# Page_E_Micro_SD.net
KiCad netlist of a schematic drawn in Altium Designer
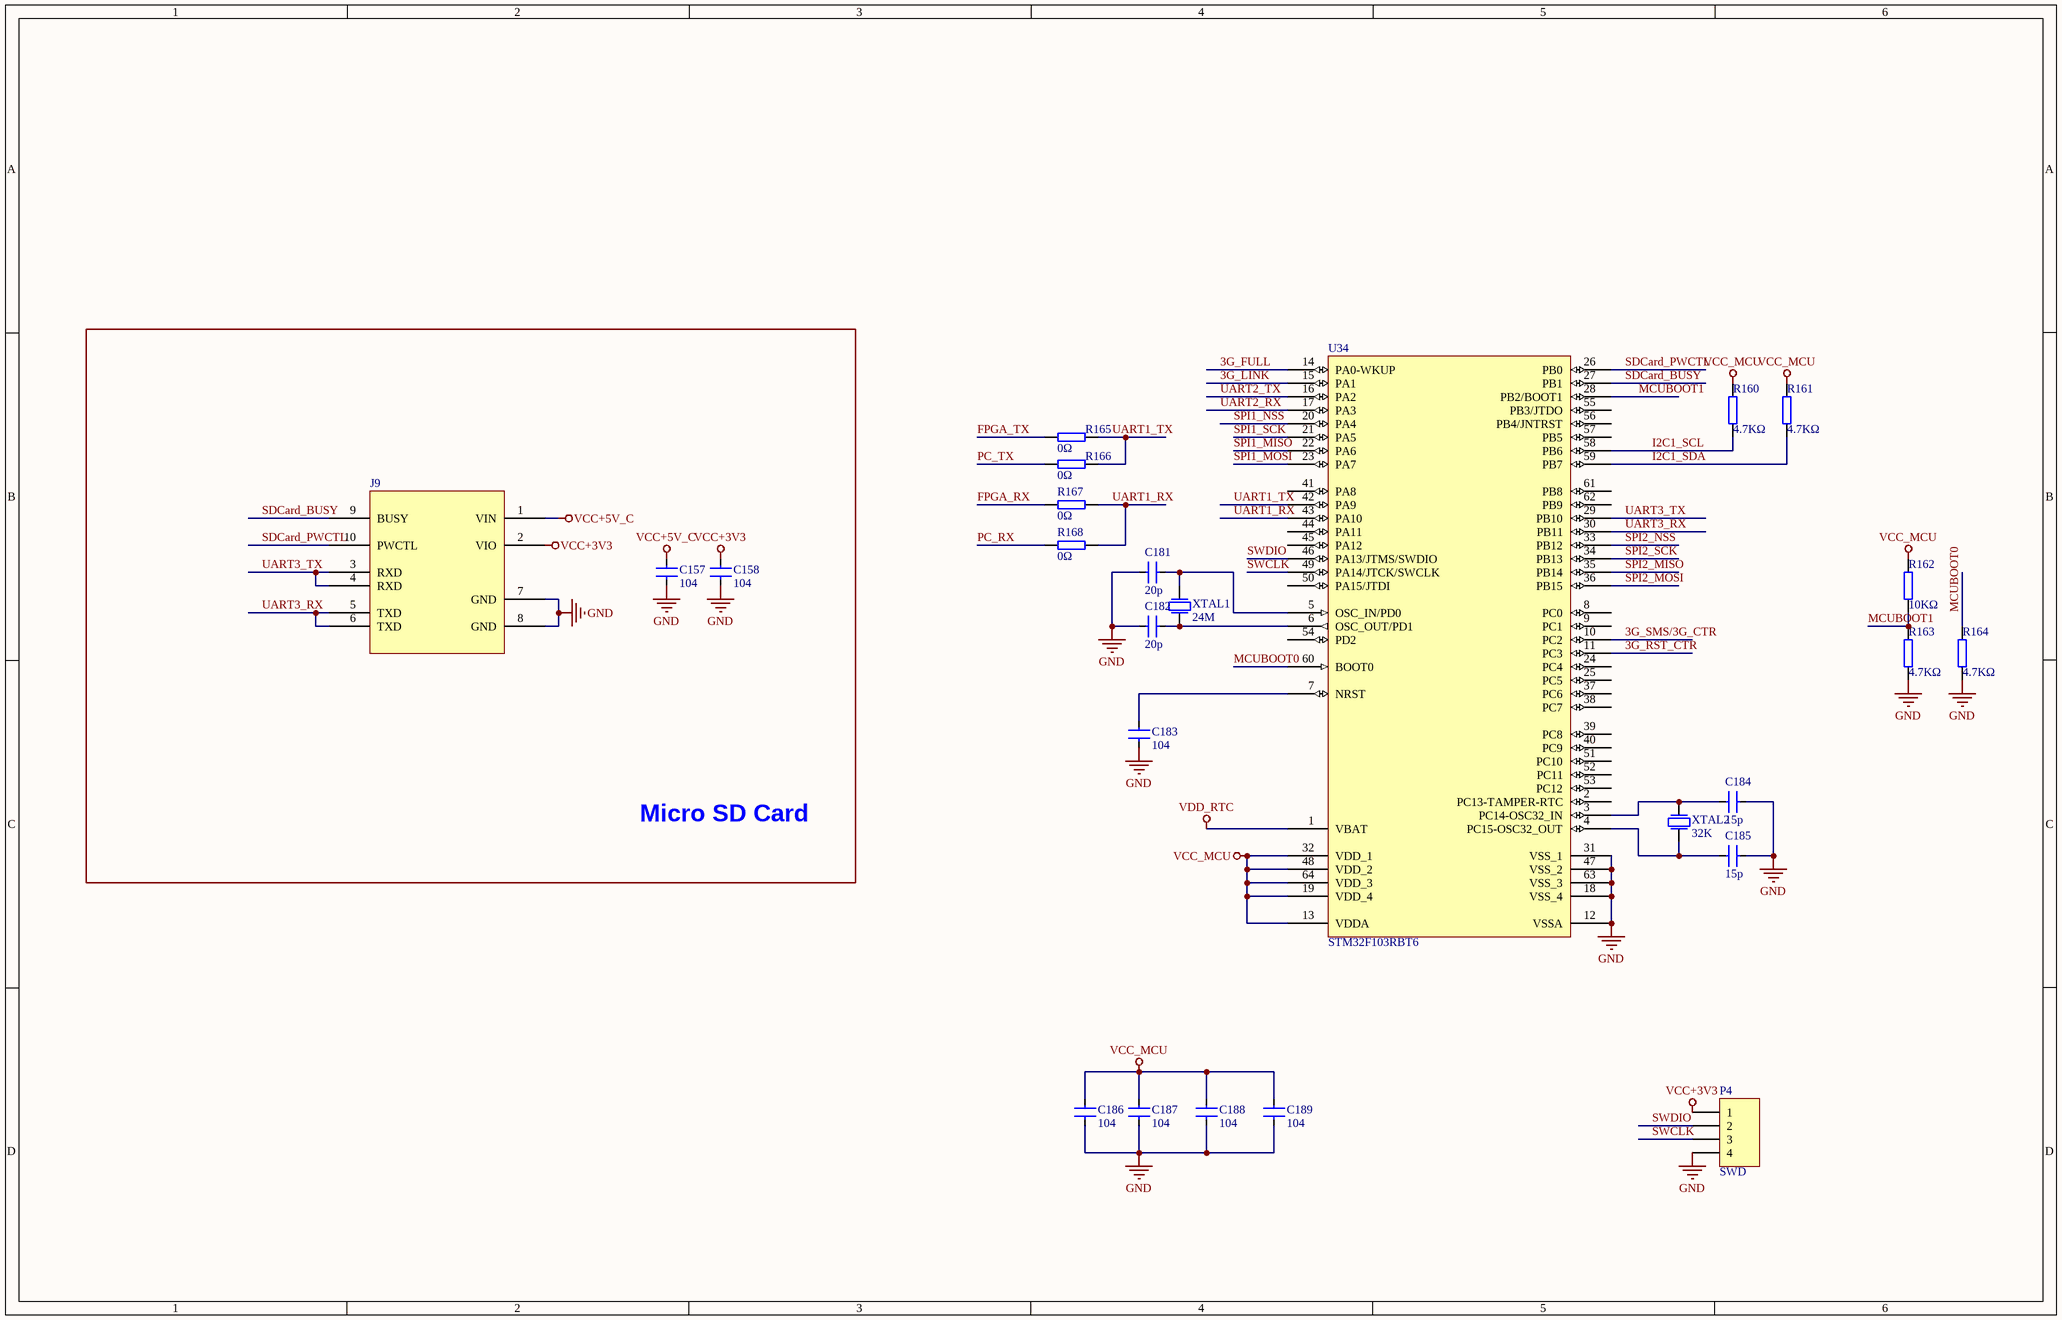
[diagram p0: Page E_Micro_SD.SchDoc]

(export (version "E")
  (design (tool "Eeschema 10.0.6"))
  (components
    (comp (ref "C157")
      (value "104")
      (footprint "0603C")
      (description "C-X5R/X7R")
      (libsource (lib "贴片电阻电容") (part "C-X5R/X7R"))
    )
    (comp (ref "C158")
      (value "104")
      (footprint "0603C")
      (description "C-X5R/X7R")
      (libsource (lib "贴片电阻电容") (part "C-X5R/X7R"))
    )
    (comp (ref "C181")
      (value "20p")
      (footprint "0603C")
      (description "C-X5R/X7R")
      (libsource (lib "贴片电阻电容") (part "C-X5R/X7R"))
    )
    (comp (ref "C182")
      (value "20p")
      (footprint "0603C")
      (description "C-X5R/X7R")
      (libsource (lib "贴片电阻电容") (part "C-X5R/X7R"))
    )
    (comp (ref "C183")
      (value "104")
      (footprint "0603C")
      (description "C-X5R/X7R")
      (libsource (lib "贴片电阻电容") (part "C-X5R/X7R"))
    )
    (comp (ref "C184")
      (value "15p")
      (footprint "0603C")
      (description "C-X5R/X7R")
      (libsource (lib "贴片电阻电容") (part "C-X5R/X7R"))
    )
    (comp (ref "C185")
      (value "15p")
      (footprint "0603C")
      (description "C-X5R/X7R")
      (libsource (lib "贴片电阻电容") (part "C-X5R/X7R"))
    )
    (comp (ref "C186")
      (value "104")
      (footprint "0603C")
      (description "C-X5R/X7R")
      (libsource (lib "贴片电阻电容") (part "C-X5R/X7R"))
    )
    (comp (ref "C187")
      (value "104")
      (footprint "0603C")
      (description "C-X5R/X7R")
      (libsource (lib "贴片电阻电容") (part "C-X5R/X7R"))
    )
    (comp (ref "C188")
      (value "104")
      (footprint "0603C")
      (description "C-X5R/X7R")
      (libsource (lib "贴片电阻电容") (part "C-X5R/X7R"))
    )
    (comp (ref "C189")
      (value "104")
      (footprint "0603C")
      (description "C-X5R/X7R")
      (libsource (lib "贴片电阻电容") (part "C-X5R/X7R"))
    )
    (comp (ref "J9") (value "SDV600") (footprint "JTAG10PW") (libsource (lib "其他元器件") (part "Uart0_SDCard")))
    (comp (ref "P4")
      (value "SWD")
      (footprint "HDR1X4")
      (description "Header, 4-Pin")
      (fields (field (name "PUBLISHER") "Altium Limited"))
      (libsource (lib "Miscellaneous Connectors") (part "Header 4"))
    )
    (comp (ref "R160") (value "4.7KΩ") (footprint "0603R") (libsource (lib "贴片电阻") (part "1K-0805R")))
    (comp (ref "R161") (value "4.7KΩ") (footprint "0603R") (libsource (lib "贴片电阻") (part "1K-0805R")))
    (comp (ref "R162") (value "10KΩ") (footprint "0603R") (libsource (lib "贴片电阻") (part "1K-0805R")))
    (comp (ref "R163") (value "4.7KΩ") (footprint "0603R") (libsource (lib "贴片电阻") (part "1K-0805R")))
    (comp (ref "R164") (value "4.7KΩ") (footprint "0603R") (libsource (lib "贴片电阻") (part "1K-0805R")))
    (comp (ref "R165") (value "0Ω") (footprint "0603R") (libsource (lib "贴片电阻") (part "1K-0805R")))
    (comp (ref "R166") (value "0Ω") (footprint "0603R") (libsource (lib "贴片电阻") (part "1K-0805R")))
    (comp (ref "R167") (value "0Ω") (footprint "0603R") (libsource (lib "贴片电阻") (part "1K-0805R")))
    (comp (ref "R168") (value "0Ω") (footprint "0603R") (libsource (lib "贴片电阻") (part "1K-0805R")))
    (comp (ref "U34")
      (value "STM32F103RBT6")
      (footprint "LQFP64_N")
      (description "STM32 ARM-based 32-bit MCU with 128 Kbytes Flash, 64-pin LQFP, Industrial Temperature")
      (fields (field (name "PUBLISHER") "Altium Limited"))
      (libsource (lib "ST Microcontroller 32-Bit STM32") (part "STM32F103RBT6"))
    )
    (comp (ref "XTAL1")
      (value "24M")
      (footprint "XTAL2")
      (description "CRYSTAL")
      (libsource (lib "xubaolong") (part "XTAL"))
    )
    (comp (ref "XTAL2")
      (value "32K")
      (footprint "XTAL_32.768")
      (description "CRYSTAL")
      (libsource (lib "xubaolong") (part "XTAL"))
    )
  )
  (nets
    (net (code "1") (name "/3G_FULL") (class "Default")
      (node (ref "U34") (pin "14") (pinfunction "PA0-WKUP_14") (pintype "bidirectional"))
    )
    (net (code "2") (name "/3G_LINK") (class "Default")
      (node (ref "U34") (pin "15") (pinfunction "PA1_15") (pintype "bidirectional"))
    )
    (net (code "3") (name "/3G_RST_CTR") (class "Default")
      (node (ref "U34") (pin "11") (pinfunction "PC3_11") (pintype "bidirectional"))
    )
    (net (code "4") (name "/3G_SMS{slash}3G_CTR") (class "Default")
      (node (ref "U34") (pin "10") (pinfunction "PC2_10") (pintype "bidirectional"))
    )
    (net (code "5") (name "/FPGA_RX") (class "Default")
      (node (ref "R167") (pin "1") (pinfunction "1_1") (pintype "passive"))
    )
    (net (code "6") (name "/FPGA_TX") (class "Default")
      (node (ref "R165") (pin "1") (pinfunction "1_1") (pintype "passive"))
    )
    (net (code "7") (name "/I2C1_SCL") (class "Default")
      (node (ref "R160") (pin "2") (pinfunction "2_2") (pintype "passive"))
      (node (ref "U34") (pin "58") (pinfunction "PB6_58") (pintype "bidirectional"))
    )
    (net (code "8") (name "/I2C1_SDA") (class "Default")
      (node (ref "R161") (pin "2") (pinfunction "2_2") (pintype "passive"))
      (node (ref "U34") (pin "59") (pinfunction "PB7_59") (pintype "bidirectional"))
    )
    (net (code "9") (name "/MCUBOOT0") (class "Default")
      (node (ref "R164") (pin "1") (pinfunction "1_1") (pintype "passive"))
      (node (ref "U34") (pin "60") (pinfunction "BOOT0_60") (pintype "input"))
    )
    (net (code "10") (name "/MCUBOOT1") (class "Default")
      (node (ref "R162") (pin "2") (pinfunction "2_2") (pintype "passive"))
      (node (ref "R163") (pin "1") (pinfunction "1_1") (pintype "passive"))
      (node (ref "U34") (pin "28") (pinfunction "PB2/BOOT1_28") (pintype "bidirectional"))
    )
    (net (code "11") (name "/PC_RX") (class "Default")
      (node (ref "R168") (pin "1") (pinfunction "1_1") (pintype "passive"))
    )
    (net (code "12") (name "/PC_TX") (class "Default")
      (node (ref "R166") (pin "1") (pinfunction "1_1") (pintype "passive"))
    )
    (net (code "13") (name "/SDCard_BUSY") (class "Default")
      (node (ref "J9") (pin "9") (pinfunction "BUSY_9") (pintype "passive"))
      (node (ref "U34") (pin "27") (pinfunction "PB1_27") (pintype "bidirectional"))
    )
    (net (code "14") (name "/SDCard_PWCTL") (class "Default")
      (node (ref "J9") (pin "10") (pinfunction "PWCTL_10") (pintype "passive"))
      (node (ref "U34") (pin "26") (pinfunction "PB0_26") (pintype "bidirectional"))
    )
    (net (code "15") (name "/SPI1_MISO") (class "Default")
      (node (ref "U34") (pin "22") (pinfunction "PA6_22") (pintype "bidirectional"))
    )
    (net (code "16") (name "/SPI1_MOSI") (class "Default")
      (node (ref "U34") (pin "23") (pinfunction "PA7_23") (pintype "bidirectional"))
    )
    (net (code "17") (name "/SPI1_NSS") (class "Default")
      (node (ref "U34") (pin "20") (pinfunction "PA4_20") (pintype "bidirectional"))
    )
    (net (code "18") (name "/SPI1_SCK") (class "Default")
      (node (ref "U34") (pin "21") (pinfunction "PA5_21") (pintype "bidirectional"))
    )
    (net (code "19") (name "/SPI2_MISO") (class "Default")
      (node (ref "U34") (pin "35") (pinfunction "PB14_35") (pintype "bidirectional"))
    )
    (net (code "20") (name "/SPI2_MOSI") (class "Default")
      (node (ref "U34") (pin "36") (pinfunction "PB15_36") (pintype "bidirectional"))
    )
    (net (code "21") (name "/SPI2_NSS") (class "Default")
      (node (ref "U34") (pin "33") (pinfunction "PB12_33") (pintype "bidirectional"))
    )
    (net (code "22") (name "/SPI2_SCK") (class "Default")
      (node (ref "U34") (pin "34") (pinfunction "PB13_34") (pintype "bidirectional"))
    )
    (net (code "23") (name "/SWCLK") (class "Default")
      (node (ref "P4") (pin "3") (pinfunction "3_3") (pintype "passive"))
      (node (ref "U34") (pin "49") (pinfunction "PA14/JTCK/SWCLK_49") (pintype "bidirectional"))
    )
    (net (code "24") (name "/SWDIO") (class "Default")
      (node (ref "P4") (pin "2") (pinfunction "2_2") (pintype "passive"))
      (node (ref "U34") (pin "46") (pinfunction "PA13/JTMS/SWDIO_46") (pintype "bidirectional"))
    )
    (net (code "25") (name "/UART1_RX") (class "Default")
      (node (ref "R167") (pin "2") (pinfunction "2_2") (pintype "passive"))
      (node (ref "R168") (pin "2") (pinfunction "2_2") (pintype "passive"))
      (node (ref "U34") (pin "43") (pinfunction "PA10_43") (pintype "bidirectional"))
    )
    (net (code "26") (name "/UART1_TX") (class "Default")
      (node (ref "R165") (pin "2") (pinfunction "2_2") (pintype "passive"))
      (node (ref "R166") (pin "2") (pinfunction "2_2") (pintype "passive"))
      (node (ref "U34") (pin "42") (pinfunction "PA9_42") (pintype "bidirectional"))
    )
    (net (code "27") (name "/UART2_RX") (class "Default")
      (node (ref "U34") (pin "17") (pinfunction "PA3_17") (pintype "bidirectional"))
    )
    (net (code "28") (name "/UART2_TX") (class "Default")
      (node (ref "U34") (pin "16") (pinfunction "PA2_16") (pintype "bidirectional"))
    )
    (net (code "29") (name "/UART3_RX") (class "Default")
      (node (ref "J9") (pin "5") (pinfunction "TXD_5") (pintype "passive"))
      (node (ref "J9") (pin "6") (pinfunction "TXD_6") (pintype "passive"))
      (node (ref "U34") (pin "30") (pinfunction "PB11_30") (pintype "bidirectional"))
    )
    (net (code "30") (name "/UART3_TX") (class "Default")
      (node (ref "J9") (pin "3") (pinfunction "RXD_3") (pintype "passive"))
      (node (ref "J9") (pin "4") (pinfunction "RXD_4") (pintype "passive"))
      (node (ref "U34") (pin "29") (pinfunction "PB10_29") (pintype "bidirectional"))
    )
    (net (code "31") (name "GND") (class "Default")
      (node (ref "C157") (pin "1") (pinfunction "1_1") (pintype "passive"))
      (node (ref "C158") (pin "1") (pinfunction "1_1") (pintype "passive"))
      (node (ref "C181") (pin "2") (pinfunction "2_2") (pintype "passive"))
      (node (ref "C182") (pin "2") (pinfunction "2_2") (pintype "passive"))
      (node (ref "C183") (pin "1") (pinfunction "1_1") (pintype "passive"))
      (node (ref "C184") (pin "1") (pinfunction "1_1") (pintype "passive"))
      (node (ref "C185") (pin "1") (pinfunction "1_1") (pintype "passive"))
      (node (ref "C186") (pin "1") (pinfunction "1_1") (pintype "passive"))
      (node (ref "C187") (pin "1") (pinfunction "1_1") (pintype "passive"))
      (node (ref "C188") (pin "1") (pinfunction "1_1") (pintype "passive"))
      (node (ref "C189") (pin "1") (pinfunction "1_1") (pintype "passive"))
      (node (ref "J9") (pin "7") (pinfunction "GND_7") (pintype "passive"))
      (node (ref "J9") (pin "8") (pinfunction "GND_8") (pintype "passive"))
      (node (ref "P4") (pin "4") (pinfunction "4_4") (pintype "passive"))
      (node (ref "R163") (pin "2") (pinfunction "2_2") (pintype "passive"))
      (node (ref "R164") (pin "2") (pinfunction "2_2") (pintype "passive"))
      (node (ref "U34") (pin "12") (pinfunction "VSSA_12") (pintype "power_in"))
      (node (ref "U34") (pin "18") (pinfunction "VSS_4_18") (pintype "power_in"))
      (node (ref "U34") (pin "31") (pinfunction "VSS_1_31") (pintype "power_in"))
      (node (ref "U34") (pin "47") (pinfunction "VSS_2_47") (pintype "power_in"))
      (node (ref "U34") (pin "63") (pinfunction "VSS_3_63") (pintype "power_in"))
    )
    (net (code "32") (name "Net-(U34-NRST)") (class "Default")
      (node (ref "C183") (pin "2") (pinfunction "2_2") (pintype "passive"))
      (node (ref "U34") (pin "7") (pinfunction "NRST_7") (pintype "bidirectional"))
    )
    (net (code "33") (name "Net-(U34-OSC_IN{slash}PD0)") (class "Default")
      (node (ref "C181") (pin "1") (pinfunction "1_1") (pintype "passive"))
      (node (ref "U34") (pin "5") (pinfunction "OSC_IN/PD0_5") (pintype "input"))
      (node (ref "XTAL1") (pin "1") (pinfunction "P1_1") (pintype "passive"))
    )
    (net (code "34") (name "Net-(U34-OSC_OUT{slash}PD1)") (class "Default")
      (node (ref "C182") (pin "1") (pinfunction "1_1") (pintype "passive"))
      (node (ref "U34") (pin "6") (pinfunction "OSC_OUT/PD1_6") (pintype "output"))
      (node (ref "XTAL1") (pin "2") (pinfunction "P2_2") (pintype "passive"))
    )
    (net (code "35") (name "Net-(U34-PC14-OSC32_IN)") (class "Default")
      (node (ref "C184") (pin "2") (pinfunction "2_2") (pintype "passive"))
      (node (ref "U34") (pin "3") (pinfunction "PC14-OSC32_IN_3") (pintype "bidirectional"))
      (node (ref "XTAL2") (pin "1") (pinfunction "P1_1") (pintype "passive"))
    )
    (net (code "36") (name "Net-(U34-PC15-OSC32_OUT)") (class "Default")
      (node (ref "C185") (pin "2") (pinfunction "2_2") (pintype "passive"))
      (node (ref "U34") (pin "4") (pinfunction "PC15-OSC32_OUT_4") (pintype "bidirectional"))
      (node (ref "XTAL2") (pin "2") (pinfunction "P2_2") (pintype "passive"))
    )
    (net (code "37") (name "VCC+3V3") (class "Default")
      (node (ref "C158") (pin "2") (pinfunction "2_2") (pintype "passive"))
      (node (ref "J9") (pin "2") (pinfunction "VIO_2") (pintype "passive"))
      (node (ref "P4") (pin "1") (pinfunction "1_1") (pintype "passive"))
    )
    (net (code "38") (name "VCC+5V_C") (class "Default")
      (node (ref "C157") (pin "2") (pinfunction "2_2") (pintype "passive"))
      (node (ref "J9") (pin "1") (pinfunction "VIN_1") (pintype "passive"))
    )
    (net (code "39") (name "VCC_MCU") (class "Default")
      (node (ref "C186") (pin "2") (pinfunction "2_2") (pintype "passive"))
      (node (ref "C187") (pin "2") (pinfunction "2_2") (pintype "passive"))
      (node (ref "C188") (pin "2") (pinfunction "2_2") (pintype "passive"))
      (node (ref "C189") (pin "2") (pinfunction "2_2") (pintype "passive"))
      (node (ref "R160") (pin "1") (pinfunction "1_1") (pintype "passive"))
      (node (ref "R161") (pin "1") (pinfunction "1_1") (pintype "passive"))
      (node (ref "R162") (pin "1") (pinfunction "1_1") (pintype "passive"))
      (node (ref "U34") (pin "13") (pinfunction "VDDA_13") (pintype "power_in"))
      (node (ref "U34") (pin "19") (pinfunction "VDD_4_19") (pintype "power_in"))
      (node (ref "U34") (pin "32") (pinfunction "VDD_1_32") (pintype "power_in"))
      (node (ref "U34") (pin "48") (pinfunction "VDD_2_48") (pintype "power_in"))
      (node (ref "U34") (pin "64") (pinfunction "VDD_3_64") (pintype "power_in"))
    )
    (net (code "40") (name "VDD_RTC") (class "Default")
      (node (ref "U34") (pin "1") (pinfunction "VBAT_1") (pintype "power_in"))
    )
    (net (code "41") (name "unconnected-(U34-PA8-Pad41)") (class "Default")
      (node (ref "U34") (pin "41") (pinfunction "PA8_41") (pintype "bidirectional"))
    )
    (net (code "42") (name "unconnected-(U34-PA11-Pad44)") (class "Default")
      (node (ref "U34") (pin "44") (pinfunction "PA11_44") (pintype "bidirectional"))
    )
    (net (code "43") (name "unconnected-(U34-PA12-Pad45)") (class "Default")
      (node (ref "U34") (pin "45") (pinfunction "PA12_45") (pintype "bidirectional"))
    )
    (net (code "44") (name "unconnected-(U34-PA15{slash}JTDI-Pad50)") (class "Default")
      (node (ref "U34") (pin "50") (pinfunction "PA15/JTDI_50") (pintype "bidirectional"))
    )
    (net (code "45") (name "unconnected-(U34-PB3{slash}JTDO-Pad55)") (class "Default")
      (node (ref "U34") (pin "55") (pinfunction "PB3/JTDO_55") (pintype "bidirectional"))
    )
    (net (code "46") (name "unconnected-(U34-PB4{slash}JNTRST-Pad56)") (class "Default")
      (node (ref "U34") (pin "56") (pinfunction "PB4/JNTRST_56") (pintype "bidirectional"))
    )
    (net (code "47") (name "unconnected-(U34-PB5-Pad57)") (class "Default")
      (node (ref "U34") (pin "57") (pinfunction "PB5_57") (pintype "bidirectional"))
    )
    (net (code "48") (name "unconnected-(U34-PB8-Pad61)") (class "Default")
      (node (ref "U34") (pin "61") (pinfunction "PB8_61") (pintype "bidirectional"))
    )
    (net (code "49") (name "unconnected-(U34-PB9-Pad62)") (class "Default")
      (node (ref "U34") (pin "62") (pinfunction "PB9_62") (pintype "bidirectional"))
    )
    (net (code "50") (name "unconnected-(U34-PC0-Pad8)") (class "Default")
      (node (ref "U34") (pin "8") (pinfunction "PC0_8") (pintype "bidirectional"))
    )
    (net (code "51") (name "unconnected-(U34-PC1-Pad9)") (class "Default")
      (node (ref "U34") (pin "9") (pinfunction "PC1_9") (pintype "bidirectional"))
    )
    (net (code "52") (name "unconnected-(U34-PC4-Pad24)") (class "Default")
      (node (ref "U34") (pin "24") (pinfunction "PC4_24") (pintype "bidirectional"))
    )
    (net (code "53") (name "unconnected-(U34-PC5-Pad25)") (class "Default")
      (node (ref "U34") (pin "25") (pinfunction "PC5_25") (pintype "bidirectional"))
    )
    (net (code "54") (name "unconnected-(U34-PC6-Pad37)") (class "Default")
      (node (ref "U34") (pin "37") (pinfunction "PC6_37") (pintype "bidirectional"))
    )
    (net (code "55") (name "unconnected-(U34-PC7-Pad38)") (class "Default")
      (node (ref "U34") (pin "38") (pinfunction "PC7_38") (pintype "bidirectional"))
    )
    (net (code "56") (name "unconnected-(U34-PC8-Pad39)") (class "Default")
      (node (ref "U34") (pin "39") (pinfunction "PC8_39") (pintype "bidirectional"))
    )
    (net (code "57") (name "unconnected-(U34-PC9-Pad40)") (class "Default")
      (node (ref "U34") (pin "40") (pinfunction "PC9_40") (pintype "bidirectional"))
    )
    (net (code "58") (name "unconnected-(U34-PC10-Pad51)") (class "Default")
      (node (ref "U34") (pin "51") (pinfunction "PC10_51") (pintype "bidirectional"))
    )
    (net (code "59") (name "unconnected-(U34-PC11-Pad52)") (class "Default")
      (node (ref "U34") (pin "52") (pinfunction "PC11_52") (pintype "bidirectional"))
    )
    (net (code "60") (name "unconnected-(U34-PC12-Pad53)") (class "Default")
      (node (ref "U34") (pin "53") (pinfunction "PC12_53") (pintype "bidirectional"))
    )
    (net (code "61") (name "unconnected-(U34-PC13-TAMPER-RTC-Pad2)") (class "Default")
      (node (ref "U34") (pin "2") (pinfunction "PC13-TAMPER-RTC_2") (pintype "bidirectional"))
    )
    (net (code "62") (name "unconnected-(U34-PD2-Pad54)") (class "Default")
      (node (ref "U34") (pin "54") (pinfunction "PD2_54") (pintype "bidirectional"))
    )
  )
)
